# Sheet1.net
KiCad netlist of a schematic drawn in Altium Designer
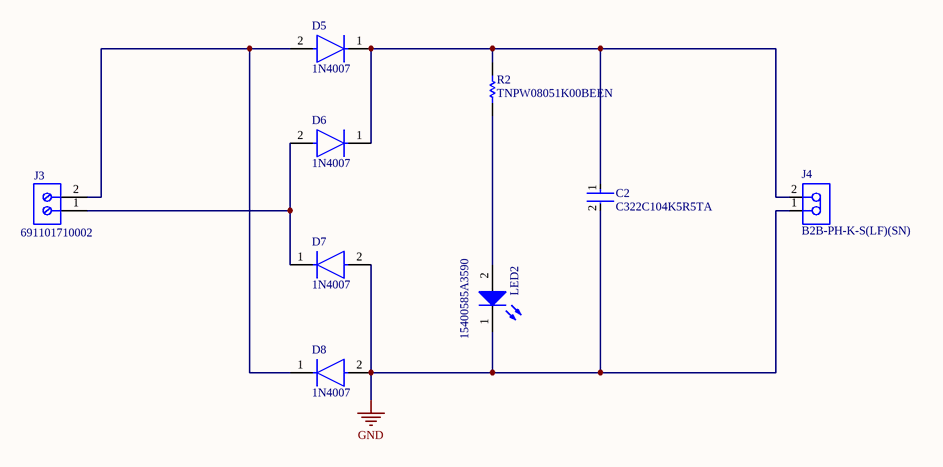
[diagram p0: Sheet1.SchDoc]

(export (version "E")
  (design (tool "Eeschema 10.0.6"))
  (components
    (comp (ref "C2")
      (value "C322C104K5R5TA")
      (footprint "FP-C322C104K5R5TA-MFG")
      (description "CAP CER 0.1UF 50V X7R RADIAL")
      (fields (field (name "TOLERANCE") "10%") (field (name "VOLTAGE") "50V"))
      (libsource (lib "Altium Content Vault") (part "b4654b650e69147ec39a6b967a45e02"))
    )
    (comp (ref "D5")
      (value "1N4007")
      (footprint "FP-1N4007-MFG")
      (description "Rectifier diode 1000 V 1 A DO-41, ,")
      (fields
        (field (name "MANUFACTURER") "Diotec")
        (field (name "OCTOPART") "https://octopart.com/1n4007-diotec-4040411")
      )
      (libsource (lib "Altium Content Vault") (part "d7152d700b627762746794eb795d46e"))
    )
    (comp (ref "D6")
      (value "1N4007")
      (footprint "FP-1N4007-MFG")
      (description "Rectifier diode 1000 V 1 A DO-41, ,")
      (fields
        (field (name "MANUFACTURER") "Diotec")
        (field (name "OCTOPART") "https://octopart.com/1n4007-diotec-4040411")
      )
      (libsource (lib "Altium Content Vault") (part "d7152d700b627762746794eb795d46e"))
    )
    (comp (ref "D7")
      (value "1N4007")
      (footprint "FP-1N4007-MFG")
      (description "Rectifier diode 1000 V 1 A DO-41, ,")
      (fields
        (field (name "MANUFACTURER") "Diotec")
        (field (name "OCTOPART") "https://octopart.com/1n4007-diotec-4040411")
      )
      (libsource (lib "Altium Content Vault") (part "d7152d700b627762746794eb795d46e"))
    )
    (comp (ref "D8")
      (value "1N4007")
      (footprint "FP-1N4007-MFG")
      (description "Rectifier diode 1000 V 1 A DO-41, ,")
      (fields
        (field (name "MANUFACTURER") "Diotec")
        (field (name "OCTOPART") "https://octopart.com/1n4007-diotec-4040411")
      )
      (libsource (lib "Altium Content Vault") (part "d7152d700b627762746794eb795d46e"))
    )
    (comp (ref "J3")
      (value "691101710002")
      (footprint "691101710002")
      (description "Conn Terminal Block 2 POS 5mm Solder ST Thru-Hole 16A Box")
      (fields (field (name "VOLTAGE") "250V"))
      (libsource (lib "Altium Content Vault") (part "TBL - 1R - 02P - Screw"))
    )
    (comp (ref "J4")
      (value "B2B-PH-K-S(LF)(SN)")
      (footprint "JST-B2B-PH-K-S_V")
      (fields (field (name "MANUFACTURER") "JST"))
      (libsource (lib "Altium Content Vault") (part "CN-2P-F-QF2"))
    )
    (comp (ref "LED2")
      (value "15400585A3590")
      (footprint "WL-TIRW_D5.8H8.6")
      (description "WL-TIRW THT Infrared Round Waterclear")
      (libsource (lib "Altium Content Vault") (part "LED_Infrared_2A-1K"))
    )
    (comp (ref "R2")
      (value "TNPW08051K00BEEN")
      (footprint "RESC2013X55X40LL15T20")
      (fields (field (name "MANUFACTURER") "Vishay Dale"))
      (libsource (lib "Altium Content Vault") (part "RES"))
    )
  )
  (nets
    (net (code "1") (name "GND") (class "Default")
      (node (ref "C2") (pin "2") (pinfunction "2_2") (pintype "passive"))
      (node (ref "D7") (pin "2") (pinfunction "A_2") (pintype "passive"))
      (node (ref "D8") (pin "2") (pinfunction "A_2") (pintype "passive"))
      (node (ref "J4") (pin "1") (pinfunction "1_1") (pintype "passive"))
      (node (ref "LED2") (pin "1") (pinfunction "K_1") (pintype "passive"))
    )
    (net (code "2") (name "Net-(D5-A)") (class "Default")
      (node (ref "D5") (pin "2") (pinfunction "A_2") (pintype "passive"))
      (node (ref "D8") (pin "1") (pinfunction "C_1") (pintype "passive"))
      (node (ref "J3") (pin "2") (pinfunction "2_2") (pintype "passive"))
    )
    (net (code "3") (name "Net-(D5-C)") (class "Default")
      (node (ref "C2") (pin "1") (pinfunction "1_1") (pintype "passive"))
      (node (ref "D5") (pin "1") (pinfunction "C_1") (pintype "passive"))
      (node (ref "D6") (pin "1") (pinfunction "C_1") (pintype "passive"))
      (node (ref "J4") (pin "2") (pinfunction "2_2") (pintype "passive"))
      (node (ref "R2") (pin "2") (pinfunction "2_2") (pintype "passive"))
    )
    (net (code "4") (name "Net-(D6-A)") (class "Default")
      (node (ref "D6") (pin "2") (pinfunction "A_2") (pintype "passive"))
      (node (ref "D7") (pin "1") (pinfunction "C_1") (pintype "passive"))
      (node (ref "J3") (pin "1") (pinfunction "1_1") (pintype "passive"))
    )
    (net (code "5") (name "Net-(LED2-A)") (class "Default")
      (node (ref "LED2") (pin "2") (pinfunction "A_2") (pintype "passive"))
      (node (ref "R2") (pin "1") (pinfunction "1_1") (pintype "passive"))
    )
  )
)
